# Booster_net_port_schematic.net
KiCad netlist of a schematic drawn in EasyEDA
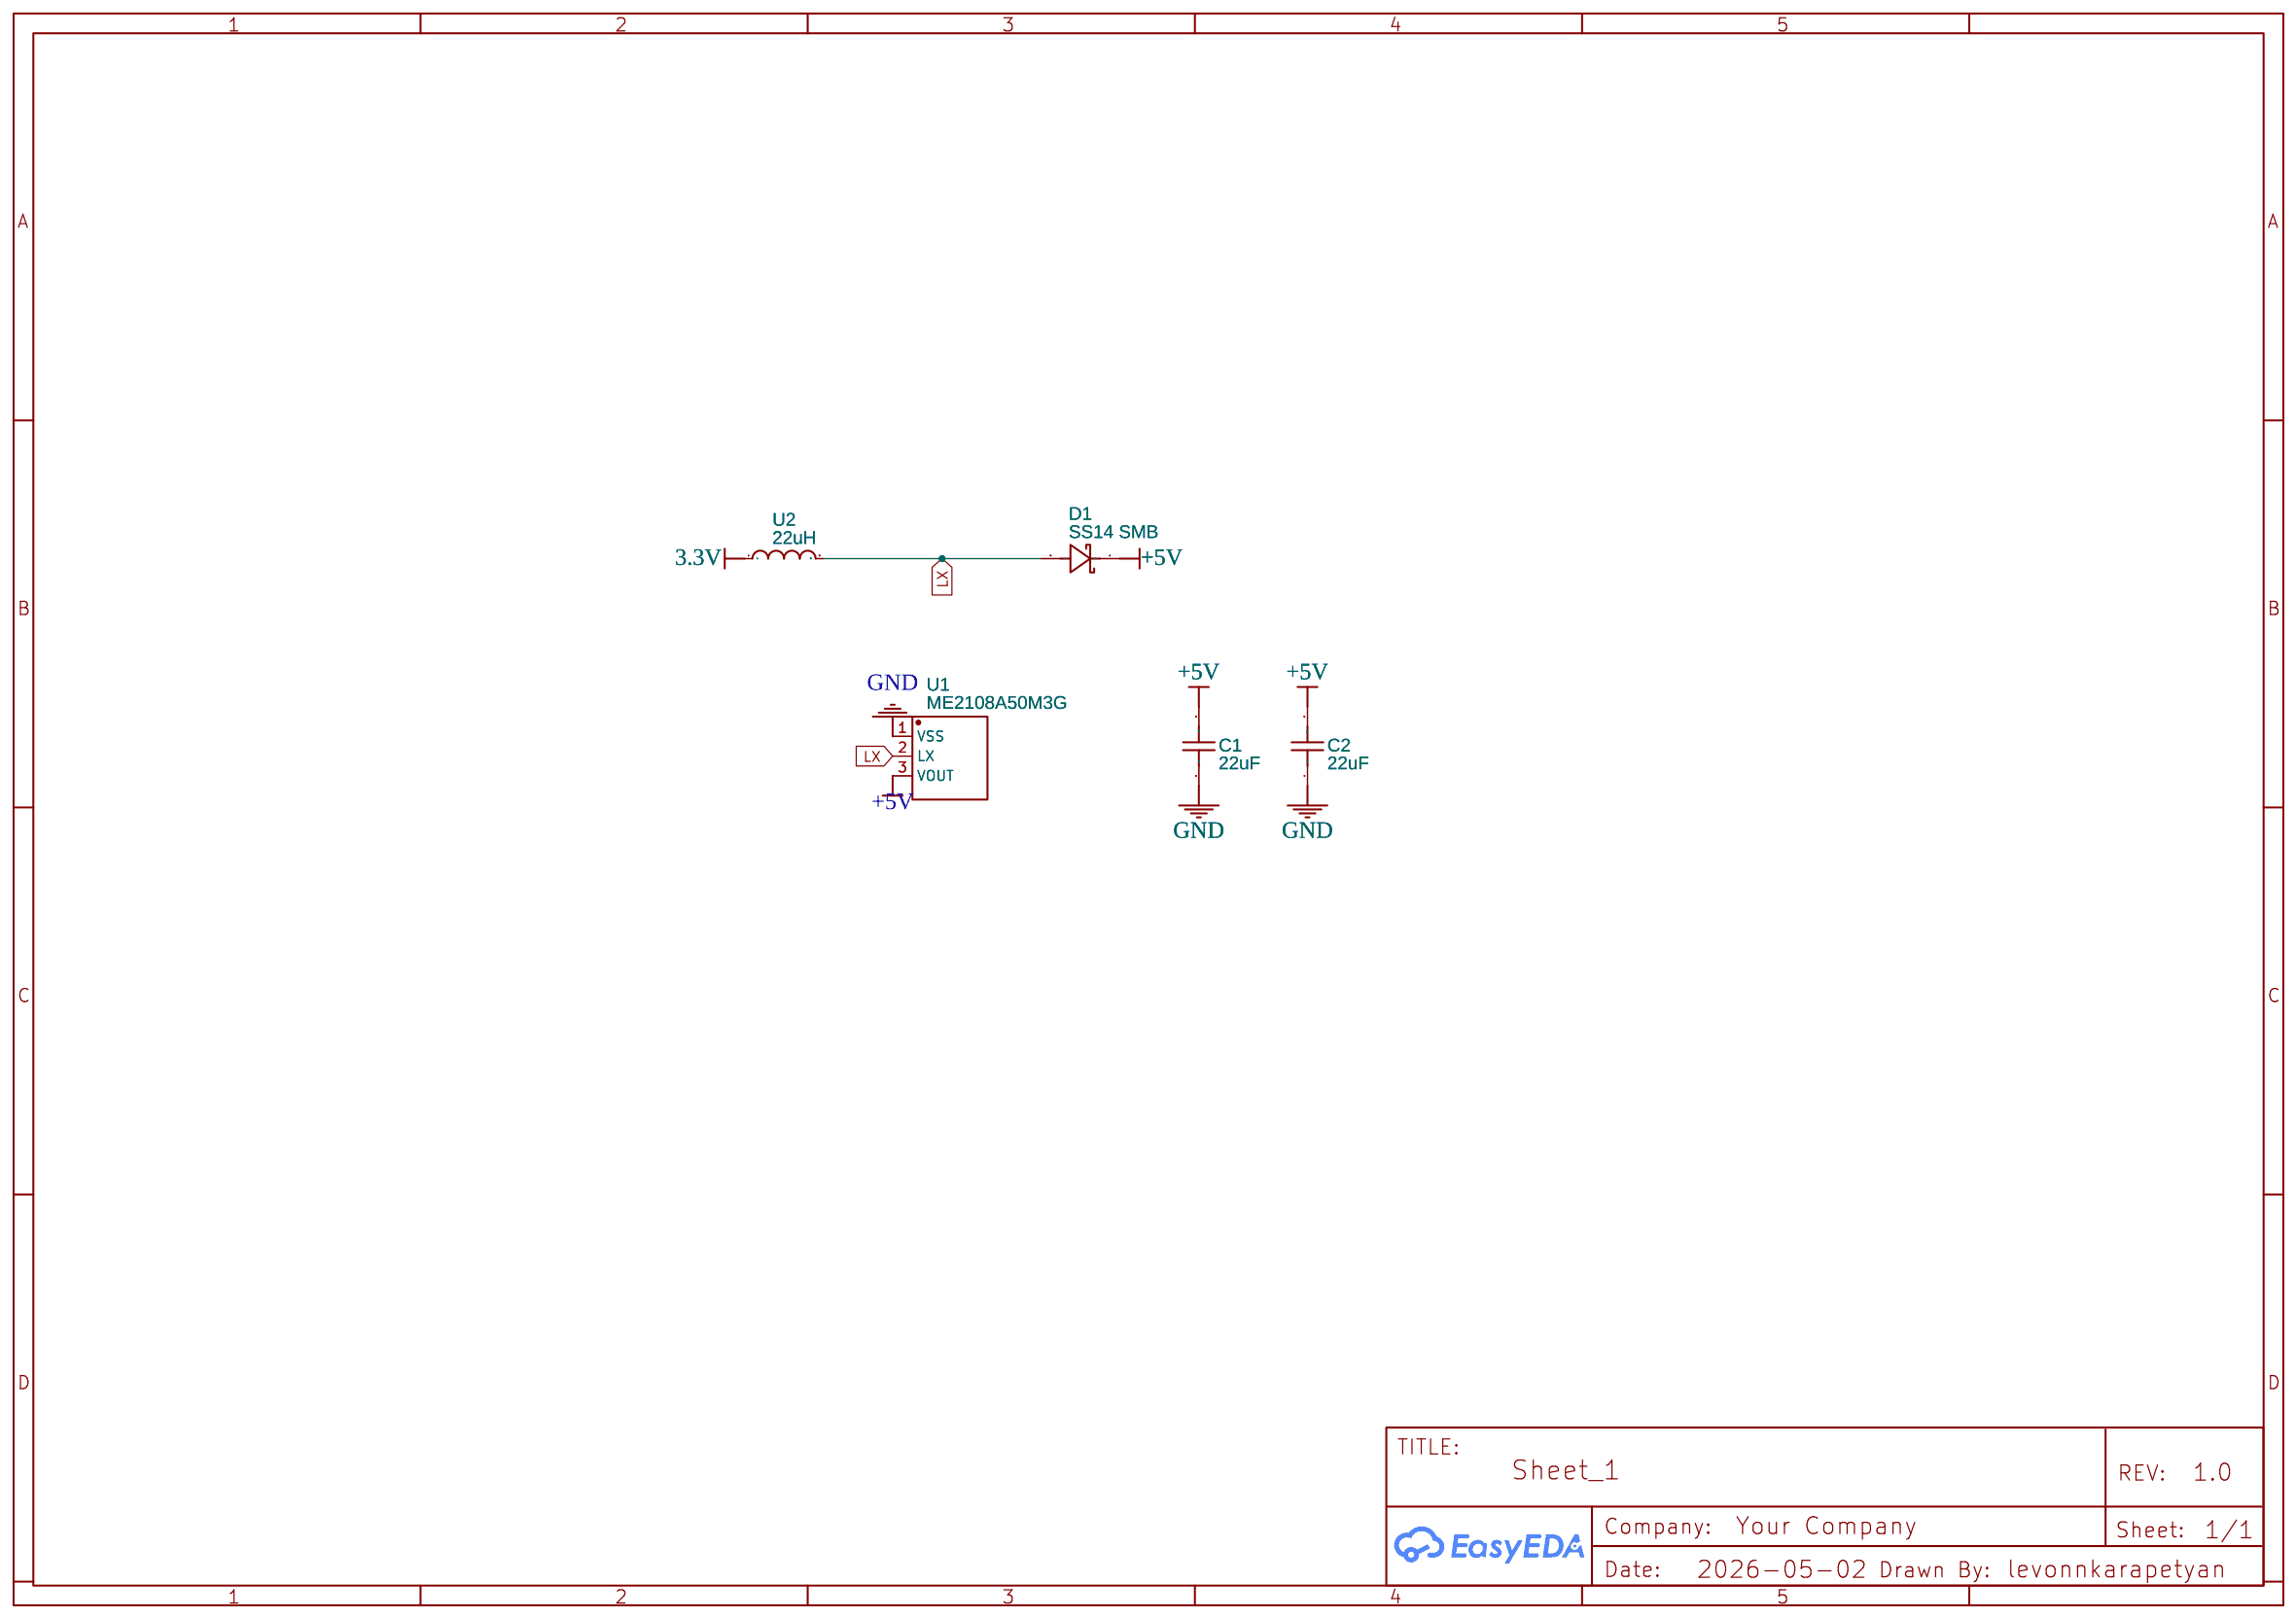
[diagram p0: schematic sheet]

(export (version "E")
  (design (tool "Eeschema 10.0.6"))
  (components
    (comp (ref "C1")
      (value "22uF")
      (fields
        (field (name "Manufacturer Part") "CL21A226MAYNNNE")
        (field (name "Manufacturer") "SAMSUNG(三星)")
      )
      (libsource (lib "") (part "CL21A226MAYNNNE"))
    )
    (comp (ref "C2")
      (value "22uF")
      (fields
        (field (name "Manufacturer Part") "CL21A226MAYNNNE")
        (field (name "Manufacturer") "SAMSUNG(三星)")
      )
      (libsource (lib "") (part "CL21A226MAYNNNE"))
    )
    (comp (ref "D1")
      (value "SS14 SMB")
      (fields (field (name "Manufacturer") "BORN(伯恩半导体)"))
      (libsource (lib "") (part "SS14 SMB"))
    )
    (comp (ref "U1")
      (value "ME2108A50M3G")
      (fields (field (name "Manufacturer") "MICRONE(南京微盟)"))
      (libsource (lib "") (part "ME2108A50M3G"))
    )
    (comp (ref "U2")
      (value "22uH")
      (fields (field (name "Manufacturer Part") "APH0630T220M") (field (name "Manufacturer") "APV(爱普微)"))
      (libsource (lib "") (part "APH0630T220M"))
    )
  )
  (nets
    (net (code "1") (name "+5V") (class "Default")
      (node (ref "C1") (pin "2") (pinfunction "2_2") (pintype "unspecified"))
      (node (ref "C2") (pin "2") (pinfunction "2_2") (pintype "unspecified"))
      (node (ref "D1") (pin "1") (pinfunction "K_1") (pintype "unspecified"))
      (node (ref "U1") (pin "3") (pinfunction "VOUT_3") (pintype "unspecified"))
    )
    (net (code "2") (name "3.3V") (class "Default")
      (node (ref "U2") (pin "1") (pinfunction "1_1") (pintype "unspecified"))
    )
    (net (code "3") (name "GND") (class "Default")
      (node (ref "C1") (pin "1") (pinfunction "1_1") (pintype "unspecified"))
      (node (ref "C2") (pin "1") (pinfunction "1_1") (pintype "unspecified"))
      (node (ref "U1") (pin "1") (pinfunction "VSS_1") (pintype "unspecified"))
    )
    (net (code "4") (name "LX") (class "Default")
      (node (ref "D1") (pin "2") (pinfunction "A_2") (pintype "unspecified"))
      (node (ref "U1") (pin "2") (pinfunction "LX_2") (pintype "unspecified"))
      (node (ref "U2") (pin "2") (pinfunction "2_2") (pintype "unspecified"))
    )
  )
)
